# magnetic-core-inductor.net
KiCad netlist of a schematic drawn in Altium Designer
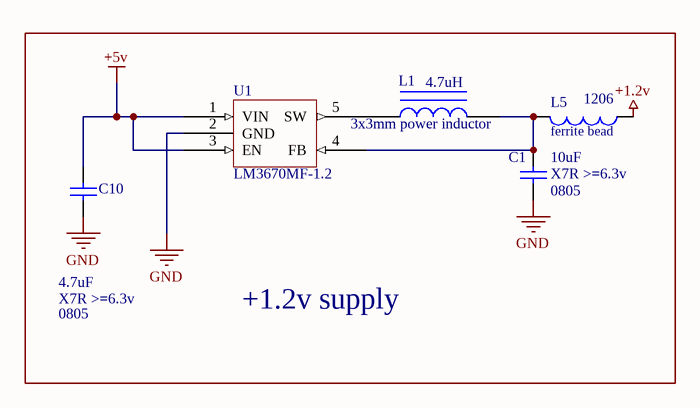
[diagram p0: magnetic-core-inductor.SchDoc]

(export (version "E")
  (design (tool "Eeschema 10.0.6"))
  (components
    (comp (ref "C1")
      (value "10uF")
      (footprint "CAPC2012N")
      (description "Capacitor (Semiconductor SIM Model)")
      (fields
        (field (name "PACKAGEREFERENCE") "0805")
        (field (name "TOLERANCE") "±10%")
        (field (name "RATING") "X7R >=6.3v")
        (field (name "Comment") "Cap Semi")
      )
      (libsource (lib "Miscellaneous Devices") (part "Cap Semi"))
    )
    (comp (ref "C10")
      (value "4.7uF")
      (footprint "CAPC2012N")
      (description "Capacitor")
      (fields
        (field (name "PACKAGEREFERENCE") "0805")
        (field (name "TOLERANCE") "-20%, +80%")
        (field (name "RATING") "X7R >=6.3v")
        (field (name "Comment") "Cap Semi")
      )
      (libsource (lib "Miscellaneous Devices") (part "Cap"))
    )
    (comp (ref "L1")
      (value "3x3mm power inductor")
      (footprint "3x3mm inductor")
      (description "Magnetic-Core Inductor")
      (fields (field (name "ALTIUM_VALUE") "4.7uH"))
      (libsource (lib "Miscellaneous Devices") (part "Inductor Iron"))
    )
    (comp (ref "L5")
      (value "ferrite bead")
      (footprint "INDC3216N")
      (description "Inductor")
      (fields (field (name "PACKAGEREFERENCE") "1206"))
      (libsource (lib "Miscellaneous Devices") (part "Inductor"))
    )
    (comp (ref "U1")
      (value "LM3670MF-1.2")
      (footprint "SOT23-5AN")
      (description "LM3670 buck step-down regulator, 350 mA")
      (fields (field (name "Comment") "LM3670MF-1.2/NOPB"))
      (libsource (lib "*") (part "LM3670"))
    )
  )
  (nets
    (net (code "1") (name "+1.2v") (class "Default")
      (node (ref "L5") (pin "1") (pinfunction "1_1") (pintype "passive"))
    )
    (net (code "2") (name "+5v") (class "Default")
      (node (ref "C10") (pin "2") (pinfunction "2_2") (pintype "passive"))
      (node (ref "U1") (pin "1") (pinfunction "VIN_1") (pintype "input"))
      (node (ref "U1") (pin "3") (pinfunction "EN_3") (pintype "input"))
    )
    (net (code "3") (name "GND") (class "Default")
      (node (ref "C1") (pin "1") (pinfunction "1_1") (pintype "passive"))
      (node (ref "C10") (pin "1") (pinfunction "1_1") (pintype "passive"))
      (node (ref "U1") (pin "2") (pinfunction "GND_2") (pintype "power_in"))
    )
    (net (code "4") (name "Net-(U1-FB)") (class "Default")
      (node (ref "C1") (pin "2") (pinfunction "2_2") (pintype "passive"))
      (node (ref "L1") (pin "2") (pinfunction "2_2") (pintype "passive"))
      (node (ref "L5") (pin "2") (pinfunction "2_2") (pintype "passive"))
      (node (ref "U1") (pin "4") (pinfunction "FB_4") (pintype "input"))
    )
    (net (code "5") (name "Net-(U1-SW)") (class "Default")
      (node (ref "L1") (pin "1") (pinfunction "1_1") (pintype "passive"))
      (node (ref "U1") (pin "5") (pinfunction "SW_5") (pintype "output"))
    )
  )
)
